# AwesomeRemote.net
KiCad netlist of a schematic drawn in Altium Designer
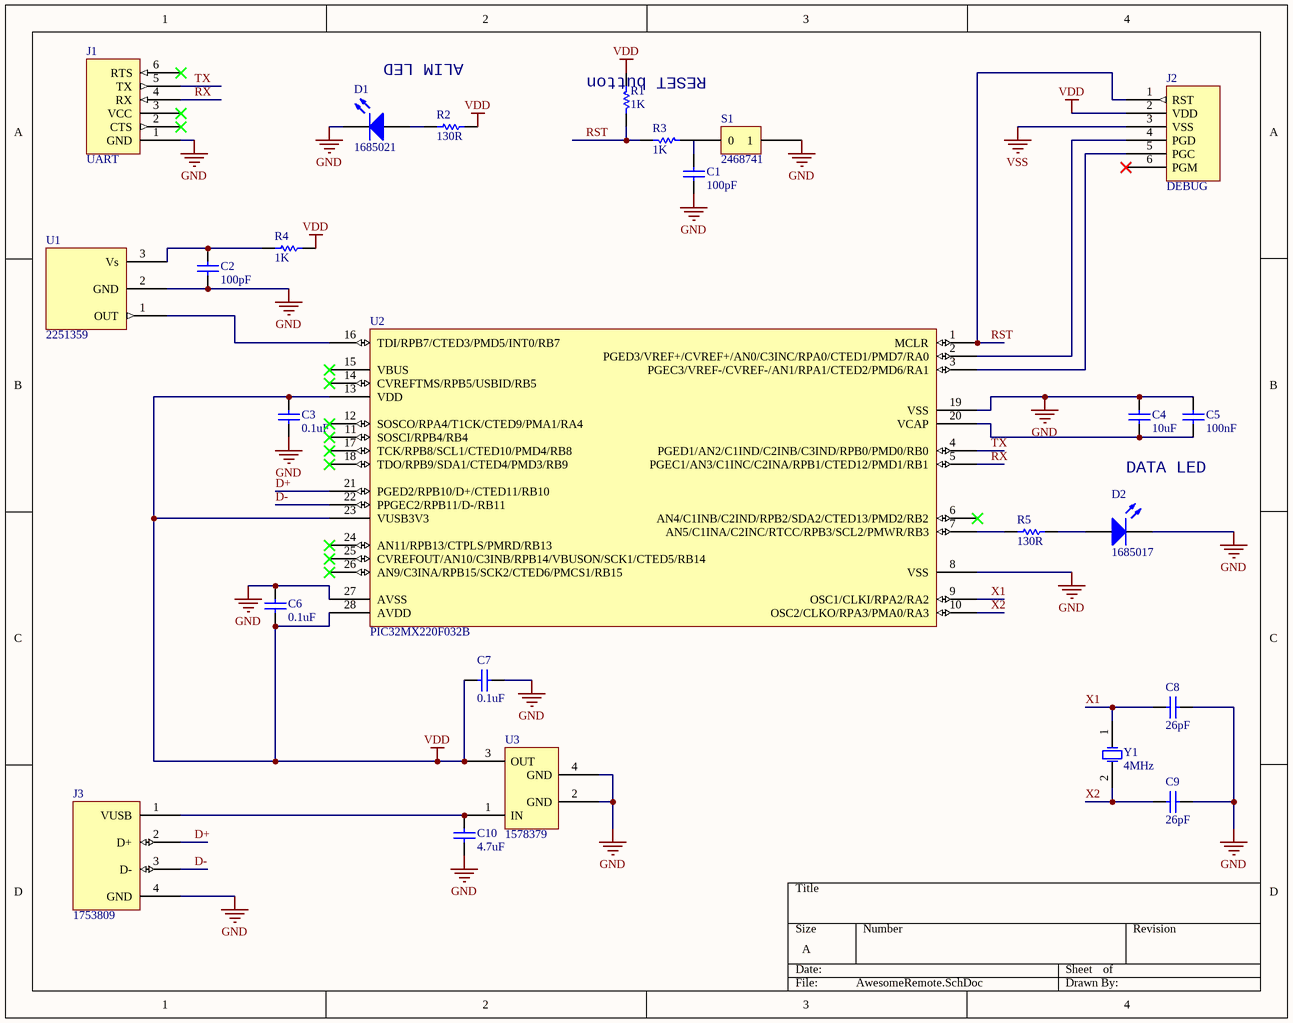
[diagram p0: AwesomeRemote.SchDoc]

(export (version "E")
  (design (tool "Eeschema 10.0.6"))
  (components
    (comp (ref "C1")
      (value "100pF")
      (footprint "CAPC1608N")
      (description "Capacitor")
      (fields (field (name "PUBLISHER") "Altium Limited"))
      (libsource (lib "AwesomeComponents") (part "Cap"))
    )
    (comp (ref "C2")
      (value "100pF")
      (footprint "CAPC1608N")
      (description "Capacitor")
      (fields (field (name "PUBLISHER") "Altium Limited"))
      (libsource (lib "AwesomeComponents") (part "Cap"))
    )
    (comp (ref "C3")
      (value "0.1uF")
      (footprint "CAPC1608N")
      (description "Capacitor")
      (fields (field (name "PUBLISHER") "Altium Limited"))
      (libsource (lib "AwesomeComponents") (part "Cap"))
    )
    (comp (ref "C4")
      (value "10uF")
      (footprint "CAPC1608N")
      (description "Capacitor")
      (fields (field (name "PUBLISHER") "Altium Limited"))
      (libsource (lib "AwesomeComponents") (part "Cap"))
    )
    (comp (ref "C5")
      (value "100nF")
      (footprint "CAPC1608N")
      (description "Capacitor")
      (fields (field (name "PUBLISHER") "Altium Limited"))
      (libsource (lib "AwesomeComponents") (part "Cap"))
    )
    (comp (ref "C6")
      (value "0.1uF")
      (footprint "CAPC1608N")
      (description "Capacitor")
      (fields (field (name "PUBLISHER") "Altium Limited"))
      (libsource (lib "AwesomeComponents") (part "Cap"))
    )
    (comp (ref "C7")
      (value "0.1uF")
      (footprint "CAPC1608N")
      (description "Capacitor")
      (fields (field (name "PUBLISHER") "Altium Limited"))
      (libsource (lib "AwesomeComponents") (part "Cap"))
    )
    (comp (ref "C8")
      (value "26pF")
      (footprint "CAPC1608N")
      (description "Capacitor")
      (fields (field (name "PUBLISHER") "Altium Limited"))
      (libsource (lib "AwesomeComponents") (part "Cap"))
    )
    (comp (ref "C9")
      (value "26pF")
      (footprint "CAPC1608N")
      (description "Capacitor")
      (fields (field (name "PUBLISHER") "Altium Limited"))
      (libsource (lib "AwesomeComponents") (part "Cap"))
    )
    (comp (ref "C10")
      (value "4.7uF")
      (footprint "CAPC1608N")
      (description "Capacitor")
      (fields (field (name "PUBLISHER") "Altium Limited"))
      (libsource (lib "AwesomeComponents") (part "Cap"))
    )
    (comp (ref "D1")
      (value "1685021")
      (footprint "LED")
      (description "Typical INFRARED GaAs LED")
      (fields (field (name "PUBLISHER") "Altium Limited"))
      (libsource (lib "AwesomeComponents") (part "LED0"))
    )
    (comp (ref "D2")
      (value "1685017")
      (footprint "LED")
      (description "Typical INFRARED GaAs LED")
      (fields (field (name "PUBLISHER") "Altium Limited"))
      (libsource (lib "AwesomeComponents") (part "LED0"))
    )
    (comp (ref "J1") (value "UART") (footprint "6-pins") (libsource (lib "AwesomeComponents") (part "CON6")))
    (comp (ref "J2")
      (value "DEBUG")
      (footprint "6-pins")
      (libsource (lib "AwesomeComponents") (part "ICD3_CON"))
    )
    (comp (ref "J3")
      (value "1753809")
      (footprint "USB_B_FEM")
      (description "USB_fem_2.0")
      (libsource (lib "AwesomeComponents") (part "USB_CON"))
    )
    (comp (ref "R1")
      (value "1K")
      (footprint "CAPC1608N")
      (description "Resistor")
      (fields (field (name "PUBLISHER") "Altium Limited"))
      (libsource (lib "AwesomeComponents") (part "Res1"))
    )
    (comp (ref "R2")
      (value "130R")
      (footprint "CAPC1608N")
      (description "Resistor")
      (fields (field (name "PUBLISHER") "Altium Limited"))
      (libsource (lib "AwesomeComponents") (part "Res1"))
    )
    (comp (ref "R3")
      (value "1K")
      (footprint "CAPC1608N")
      (description "Resistor")
      (fields (field (name "PUBLISHER") "Altium Limited"))
      (libsource (lib "AwesomeComponents") (part "Res1"))
    )
    (comp (ref "R4")
      (value "1K")
      (footprint "CAPC1608N")
      (description "Resistor")
      (fields (field (name "PUBLISHER") "Altium Limited"))
      (libsource (lib "AwesomeComponents") (part "Res1"))
    )
    (comp (ref "R5")
      (value "130R")
      (footprint "CAPC1608N")
      (description "Resistor")
      (fields (field (name "PUBLISHER") "Altium Limited"))
      (libsource (lib "AwesomeComponents") (part "Res1"))
    )
    (comp (ref "S1")
      (value "2468741")
      (footprint "PUSH_BUTTON")
      (libsource (lib "AwesomeComponents") (part "PUSH_BUT"))
    )
    (comp (ref "U1")
      (value "2251359")
      (footprint "AwesomeComponents:TSOP38238")
      (description "IR Receiver")
      (libsource (lib "AwesomeComponents") (part "TSOP38238"))
    )
    (comp (ref "U2")
      (value "PIC32MX220F032B")
      (footprint "AwesomeComponents:PIC32MX220")
      (libsource (lib "AwesomeComponents") (part "PIC32MX220F032B"))
    )
    (comp (ref "U3")
      (value "1578379")
      (footprint "AwesomeComponents:LDO_REG")
      (libsource (lib "AwesomeComponents") (part "VOLTAGE_REG"))
    )
    (comp (ref "Y1")
      (value "4MHz")
      (footprint "XTAL139X50X45")
      (description "Crystal Oscillator")
      (fields (field (name "PUBLISHER") "Altium Limited"))
      (libsource (lib "AwesomeComponents") (part "XTAL"))
    )
  )
  (nets
    (net (code "1") (name "/D+") (class "Default")
      (node (ref "J3") (pin "2") (pinfunction "D+_2") (pintype "bidirectional"))
      (node (ref "U2") (pin "21") (pinfunction "PGED2/RPB10/D+/CTED11/RB10_21") (pintype "bidirectional"))
    )
    (net (code "2") (name "/D-") (class "Default")
      (node (ref "J3") (pin "3") (pinfunction "D-_3") (pintype "bidirectional"))
      (node (ref "U2") (pin "22") (pinfunction "PPGEC2/RPB11/D-/RB11_22") (pintype "bidirectional"))
    )
    (net (code "3") (name "/RST") (class "Default")
      (node (ref "J2") (pin "1") (pinfunction "RST_1") (pintype "output"))
      (node (ref "R1") (pin "1") (pinfunction "1_1") (pintype "passive"))
      (node (ref "R3") (pin "2") (pinfunction "2_2") (pintype "passive"))
      (node (ref "U2") (pin "1") (pinfunction "MCLR_1") (pintype "bidirectional"))
    )
    (net (code "4") (name "/RX") (class "Default")
      (node (ref "J1") (pin "4") (pinfunction "RX_4") (pintype "input"))
      (node (ref "U2") (pin "5") (pinfunction "PGEC1/AN3/C1INC/C2INA/RPB1/CTED12/PMD1/RB1_5") (pintype "bidirectional"))
    )
    (net (code "5") (name "/TX") (class "Default")
      (node (ref "J1") (pin "5") (pinfunction "TX_5") (pintype "output"))
      (node (ref "U2") (pin "4") (pinfunction "PGED1/AN2/C1IND/C2INB/C3IND/RPB0/PMD0/RB0_4") (pintype "bidirectional"))
    )
    (net (code "6") (name "/X1") (class "Default")
      (node (ref "C8") (pin "1") (pinfunction "1_1") (pintype "passive"))
      (node (ref "U2") (pin "9") (pinfunction "OSC1/CLKI/RPA2/RA2_9") (pintype "bidirectional"))
      (node (ref "Y1") (pin "1") (pinfunction "OSC1_1") (pintype "passive"))
    )
    (net (code "7") (name "/X2") (class "Default")
      (node (ref "C9") (pin "1") (pinfunction "1_1") (pintype "passive"))
      (node (ref "U2") (pin "10") (pinfunction "OSC2/CLKO/RPA3/PMA0/RA3_10") (pintype "bidirectional"))
      (node (ref "Y1") (pin "2") (pinfunction "OSC2_2") (pintype "passive"))
    )
    (net (code "8") (name "GND") (class "Default")
      (node (ref "C1") (pin "1") (pinfunction "1_1") (pintype "passive"))
      (node (ref "C10") (pin "1") (pinfunction "1_1") (pintype "passive"))
      (node (ref "C2") (pin "1") (pinfunction "1_1") (pintype "passive"))
      (node (ref "C3") (pin "2") (pinfunction "2_2") (pintype "passive"))
      (node (ref "C4") (pin "1") (pinfunction "1_1") (pintype "passive"))
      (node (ref "C5") (pin "1") (pinfunction "1_1") (pintype "passive"))
      (node (ref "C6") (pin "1") (pinfunction "1_1") (pintype "passive"))
      (node (ref "C7") (pin "2") (pinfunction "2_2") (pintype "passive"))
      (node (ref "C8") (pin "2") (pinfunction "2_2") (pintype "passive"))
      (node (ref "C9") (pin "2") (pinfunction "2_2") (pintype "passive"))
      (node (ref "D1") (pin "2") (pinfunction "K_2") (pintype "passive"))
      (node (ref "D2") (pin "2") (pinfunction "K_2") (pintype "passive"))
      (node (ref "J1") (pin "1") (pinfunction "GND_1") (pintype "power_in"))
      (node (ref "J3") (pin "4") (pinfunction "GND_4") (pintype "power_in"))
      (node (ref "S1") (pin "1") (pinfunction "1_1") (pintype "power_in"))
      (node (ref "U1") (pin "2") (pinfunction "GND_2") (pintype "power_in"))
      (node (ref "U2") (pin "19") (pinfunction "VSS_19") (pintype "power_in"))
      (node (ref "U2") (pin "27") (pinfunction "AVSS_27") (pintype "power_in"))
      (node (ref "U2") (pin "8") (pinfunction "VSS_8") (pintype "power_in"))
      (node (ref "U3") (pin "2") (pinfunction "GND_2") (pintype "power_in"))
      (node (ref "U3") (pin "4") (pinfunction "GND_4") (pintype "power_in"))
    )
    (net (code "9") (name "Net-(C1-Pad2)") (class "Default")
      (node (ref "C1") (pin "2") (pinfunction "2_2") (pintype "passive"))
      (node (ref "R3") (pin "1") (pinfunction "1_1") (pintype "passive"))
    )
    (net (code "10") (name "Net-(D1-A)") (class "Default")
      (node (ref "D1") (pin "1") (pinfunction "A_1") (pintype "passive"))
      (node (ref "R2") (pin "1") (pinfunction "1_1") (pintype "passive"))
    )
    (net (code "11") (name "Net-(D2-A)") (class "Default")
      (node (ref "D2") (pin "1") (pinfunction "A_1") (pintype "passive"))
      (node (ref "R5") (pin "2") (pinfunction "2_2") (pintype "passive"))
    )
    (net (code "12") (name "Net-(J2-PGC)") (class "Default")
      (node (ref "J2") (pin "5") (pinfunction "PGC_5") (pintype "power_in"))
      (node (ref "U2") (pin "3") (pinfunction "PGEC3/VREF-/CVREF-/AN1/RPA1/CTED2/PMD6/RA1_3") (pintype "bidirectional"))
    )
    (net (code "13") (name "Net-(J2-PGD)") (class "Default")
      (node (ref "J2") (pin "4") (pinfunction "PGD_4") (pintype "power_in"))
      (node (ref "U2") (pin "2") (pinfunction "PGED3/VREF+/CVREF+/AN0/C3INC/RPA0/CTED1/PMD7/RA0_2") (pintype "bidirectional"))
    )
    (net (code "14") (name "Net-(J3-VUSB)") (class "Default")
      (node (ref "C10") (pin "2") (pinfunction "2_2") (pintype "passive"))
      (node (ref "J3") (pin "1") (pinfunction "VUSB_1") (pintype "power_in"))
      (node (ref "U3") (pin "1") (pinfunction "IN_1") (pintype "power_in"))
    )
    (net (code "15") (name "Net-(U1-OUT)") (class "Default")
      (node (ref "U1") (pin "1") (pinfunction "OUT_1") (pintype "output"))
      (node (ref "U2") (pin "16") (pinfunction "TDI/RPB7/CTED3/PMD5/INT0/RB7_16") (pintype "bidirectional"))
    )
    (net (code "16") (name "Net-(U1-Vs)") (class "Default")
      (node (ref "C2") (pin "2") (pinfunction "2_2") (pintype "passive"))
      (node (ref "R4") (pin "1") (pinfunction "1_1") (pintype "passive"))
      (node (ref "U1") (pin "3") (pinfunction "Vs_3") (pintype "power_in"))
    )
    (net (code "17") (name "Net-(U2-AN5{slash}C1INA{slash}C2INC{slash}RTCC{slash}RPB3{slash}SCL2{slash}PMWR{slash}RB3)") (class "Default")
      (node (ref "R5") (pin "1") (pinfunction "1_1") (pintype "passive"))
      (node (ref "U2") (pin "7") (pinfunction "AN5/C1INA/C2INC/RTCC/RPB3/SCL2/PMWR/RB3_7") (pintype "bidirectional"))
    )
    (net (code "18") (name "Net-(U2-VCAP)") (class "Default")
      (node (ref "C4") (pin "2") (pinfunction "2_2") (pintype "passive"))
      (node (ref "C5") (pin "2") (pinfunction "2_2") (pintype "passive"))
      (node (ref "U2") (pin "20") (pinfunction "VCAP_20") (pintype "power_in"))
    )
    (net (code "19") (name "VDD") (class "Default")
      (node (ref "C3") (pin "1") (pinfunction "1_1") (pintype "passive"))
      (node (ref "C6") (pin "2") (pinfunction "2_2") (pintype "passive"))
      (node (ref "C7") (pin "1") (pinfunction "1_1") (pintype "passive"))
      (node (ref "J2") (pin "2") (pinfunction "VDD_2") (pintype "power_in"))
      (node (ref "R1") (pin "2") (pinfunction "2_2") (pintype "passive"))
      (node (ref "R2") (pin "2") (pinfunction "2_2") (pintype "passive"))
      (node (ref "R4") (pin "2") (pinfunction "2_2") (pintype "passive"))
      (node (ref "U2") (pin "13") (pinfunction "VDD_13") (pintype "power_in"))
      (node (ref "U2") (pin "23") (pinfunction "VUSB3V3_23") (pintype "power_in"))
      (node (ref "U2") (pin "28") (pinfunction "AVDD_28") (pintype "power_in"))
      (node (ref "U3") (pin "3") (pinfunction "OUT_3") (pintype "power_in"))
    )
    (net (code "20") (name "VSS") (class "Default")
      (node (ref "J2") (pin "3") (pinfunction "VSS_3") (pintype "power_in"))
    )
    (net (code "21") (name "unconnected-(J1-CTS-Pad2)") (class "Default")
      (node (ref "J1") (pin "2") (pinfunction "CTS_2") (pintype "output+no_connect"))
    )
    (net (code "22") (name "unconnected-(J1-RTS-Pad6)") (class "Default")
      (node (ref "J1") (pin "6") (pinfunction "RTS_6") (pintype "input+no_connect"))
    )
    (net (code "23") (name "unconnected-(J1-VCC-Pad3)") (class "Default")
      (node (ref "J1") (pin "3") (pinfunction "VCC_3") (pintype "power_in+no_connect"))
    )
    (net (code "24") (name "unconnected-(J2-PGM-Pad6)") (class "Default")
      (node (ref "J2") (pin "6") (pinfunction "PGM_6") (pintype "power_in+no_connect"))
    )
    (net (code "25") (name "unconnected-(S1-Pad0)") (class "Default")
      (node (ref "S1") (pin "0") (pinfunction "0_0") (pintype "power_in"))
    )
    (net (code "26") (name "unconnected-(U2-AN4{slash}C1INB{slash}C2IND{slash}RPB2{slash}SDA2{slash}CTED13{slash}PMD2{slash}RB2-Pad6)") (class "Default")
      (node (ref "U2") (pin "6") (pinfunction "AN4/C1INB/C2IND/RPB2/SDA2/CTED13/PMD2/RB2_6") (pintype "bidirectional+no_connect"))
    )
    (net (code "27") (name "unconnected-(U2-AN9{slash}C3INA{slash}RPB15{slash}SCK2{slash}CTED6{slash}PMCS1{slash}RB15-Pad26)") (class "Default")
      (node (ref "U2") (pin "26") (pinfunction "AN9/C3INA/RPB15/SCK2/CTED6/PMCS1/RB15_26") (pintype "bidirectional+no_connect"))
    )
    (net (code "28") (name "unconnected-(U2-AN11{slash}RPB13{slash}CTPLS{slash}PMRD{slash}RB13-Pad24)") (class "Default")
      (node (ref "U2") (pin "24") (pinfunction "AN11/RPB13/CTPLS/PMRD/RB13_24") (pintype "bidirectional+no_connect"))
    )
    (net (code "29") (name "unconnected-(U2-CVREFOUT{slash}AN10{slash}C3INB{slash}RPB14{slash}VBUSON{slash}SCK1{slash}CTED5{slash}RB14-Pad25)") (class "Default")
      (node (ref "U2") (pin "25") (pinfunction "CVREFOUT/AN10/C3INB/RPB14/VBUSON/SCK1/CTED5/RB14_25") (pintype "bidirectional+no_connect"))
    )
    (net (code "30") (name "unconnected-(U2-CVREFTMS{slash}RPB5{slash}USBID{slash}RB5-Pad14)") (class "Default")
      (node (ref "U2") (pin "14") (pinfunction "CVREFTMS/RPB5/USBID/RB5_14") (pintype "bidirectional+no_connect"))
    )
    (net (code "31") (name "unconnected-(U2-SOSCI{slash}RPB4{slash}RB4-Pad11)") (class "Default")
      (node (ref "U2") (pin "11") (pinfunction "SOSCI/RPB4/RB4_11") (pintype "bidirectional+no_connect"))
    )
    (net (code "32") (name "unconnected-(U2-SOSCO{slash}RPA4{slash}T1CK{slash}CTED9{slash}PMA1{slash}RA4-Pad12)") (class "Default")
      (node (ref "U2") (pin "12") (pinfunction "SOSCO/RPA4/T1CK/CTED9/PMA1/RA4_12") (pintype "bidirectional+no_connect"))
    )
    (net (code "33") (name "unconnected-(U2-TCK{slash}RPB8{slash}SCL1{slash}CTED10{slash}PMD4{slash}RB8-Pad17)") (class "Default")
      (node (ref "U2") (pin "17") (pinfunction "TCK/RPB8/SCL1/CTED10/PMD4/RB8_17") (pintype "bidirectional+no_connect"))
    )
    (net (code "34") (name "unconnected-(U2-TDO{slash}RPB9{slash}SDA1{slash}CTED4{slash}PMD3{slash}RB9-Pad18)") (class "Default")
      (node (ref "U2") (pin "18") (pinfunction "TDO/RPB9/SDA1/CTED4/PMD3/RB9_18") (pintype "bidirectional+no_connect"))
    )
    (net (code "35") (name "unconnected-(U2-VBUS-Pad15)") (class "Default")
      (node (ref "U2") (pin "15") (pinfunction "VBUS_15") (pintype "power_in+no_connect"))
    )
  )
)
